# CH32L103C8T-R0.net
KiCad netlist of a schematic drawn in Altium Designer
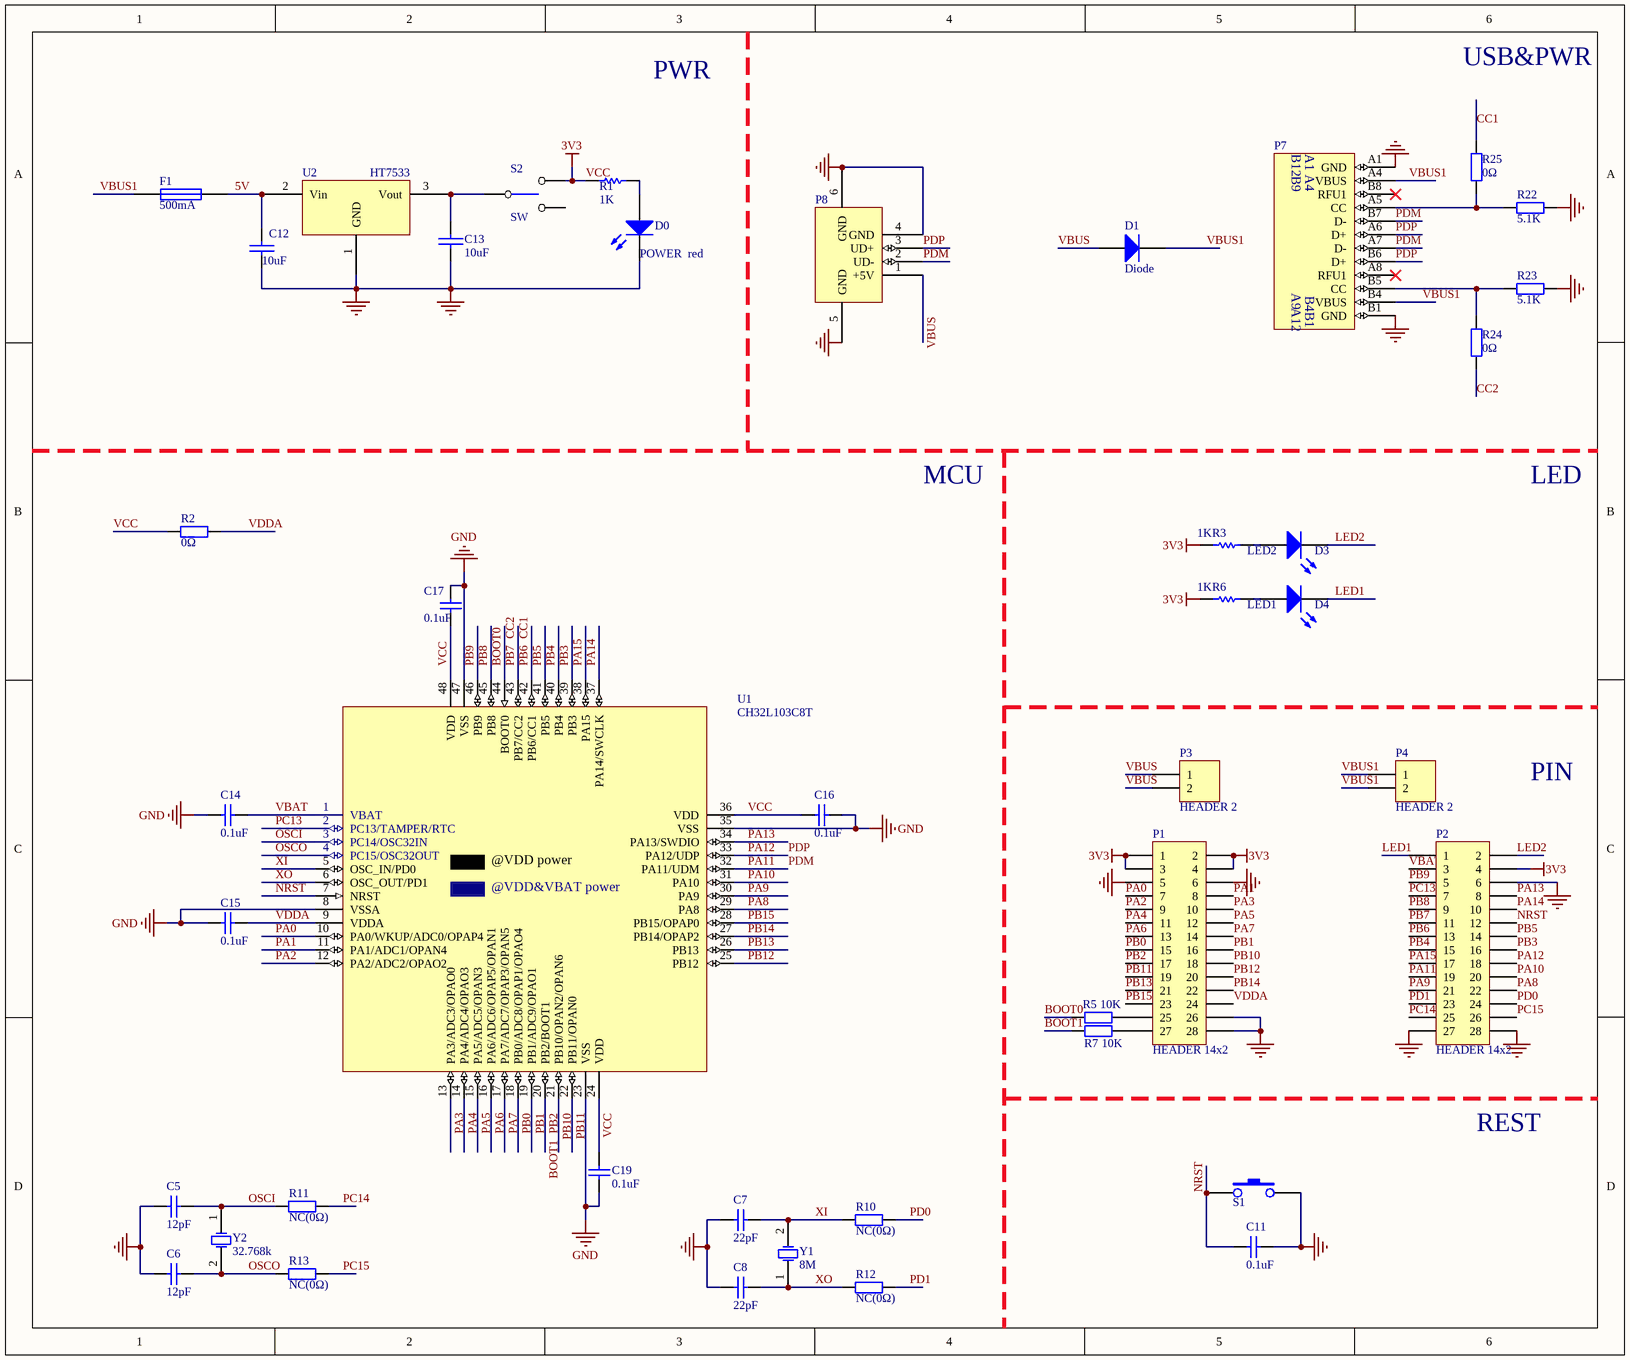
[diagram p0: CH32L103C8T-R0.SchDoc]

(export (version "E")
  (design (tool "Eeschema 10.0.6"))
  (components
    (comp (ref "C5")
      (value "12pF")
      (footprint "0402_C")
      (description "Capacitor")
      (fields (field (name "PUBLISHER") "Altium Limited"))
      (libsource (lib "*") (part "Cap"))
    )
    (comp (ref "C6")
      (value "12pF")
      (footprint "0402_C")
      (description "Capacitor")
      (fields (field (name "PUBLISHER") "Altium Limited"))
      (libsource (lib "*") (part "Cap"))
    )
    (comp (ref "C7")
      (value "22pF")
      (footprint "0402_C")
      (description "Capacitor")
      (fields (field (name "PUBLISHER") "Altium Limited"))
      (libsource (lib "*") (part "Cap"))
    )
    (comp (ref "C8")
      (value "22pF")
      (footprint "0402_C")
      (description "Capacitor")
      (fields (field (name "PUBLISHER") "Altium Limited"))
      (libsource (lib "*") (part "Cap"))
    )
    (comp (ref "C11")
      (value "0.1uF")
      (footprint "0402_C")
      (description "Capacitor")
      (fields (field (name "PUBLISHER") "Altium Limited"))
      (libsource (lib "*") (part "Cap"))
    )
    (comp (ref "C12")
      (value "10uF")
      (footprint "0603_C")
      (description "Capacitor")
      (libsource (lib "*") (part "CAP"))
    )
    (comp (ref "C13")
      (value "10uF")
      (footprint "0603_C")
      (description "Capacitor")
      (libsource (lib "*") (part "CAP"))
    )
    (comp (ref "C14")
      (value "0.1uF")
      (footprint "0402_C")
      (description "Capacitor")
      (fields (field (name "PUBLISHER") "Altium Limited"))
      (libsource (lib "*") (part "Cap"))
    )
    (comp (ref "C15")
      (value "0.1uF")
      (footprint "0402_C")
      (description "Capacitor")
      (fields (field (name "PUBLISHER") "Altium Limited"))
      (libsource (lib "*") (part "Cap"))
    )
    (comp (ref "C16")
      (value "0.1uF")
      (footprint "0402_C")
      (description "Capacitor")
      (fields (field (name "PUBLISHER") "Altium Limited"))
      (libsource (lib "*") (part "Cap"))
    )
    (comp (ref "C17")
      (value "0.1uF")
      (footprint "0402_C")
      (description "Capacitor")
      (fields (field (name "PUBLISHER") "Altium Limited"))
      (libsource (lib "*") (part "Cap"))
    )
    (comp (ref "C19")
      (value "0.1uF")
      (footprint "0402_C")
      (description "Capacitor")
      (fields (field (name "PUBLISHER") "Altium Limited"))
      (libsource (lib "*") (part "Cap"))
    )
    (comp (ref "D0")
      (value "POWER  red")
      (footprint "0603+")
      (description "Typical INFRARED GaAs LED")
      (fields (field (name "PUBLISHER") "Altium Limited"))
      (libsource (lib "*") (part "LED0"))
    )
    (comp (ref "D1")
      (value "Diode")
      (footprint "SOD-123")
      (description "Default Diode")
      (fields (field (name "PUBLISHER") "Altium Limited"))
      (libsource (lib "Miscellaneous Devices") (part "Diode"))
    )
    (comp (ref "D3")
      (value "LED2")
      (footprint "0603+")
      (description "Typical INFRARED GaAs LED")
      (fields (field (name "PUBLISHER") "Altium Limited"))
      (libsource (lib "*") (part "LED0"))
    )
    (comp (ref "D4")
      (value "LED1")
      (footprint "0603+")
      (description "Typical INFRARED GaAs LED")
      (fields (field (name "PUBLISHER") "Altium Limited"))
      (libsource (lib "*") (part "LED0"))
    )
    (comp (ref "F1")
      (value "500mA")
      (footprint "0603")
      (description "Fuse")
      (libsource (lib "*") (part "FUSE1"))
    )
    (comp (ref "P1")
      (value "HEADER 14x2")
      (footprint "MYPCB:IDC28-2.54MM")
      (description "Header, 14-Pin, Dual row")
      (libsource (lib "wch_sch_others") (part "HEADER 14x2"))
    )
    (comp (ref "P2")
      (value "HEADER 14x2")
      (footprint "MYPCB:IDC28-2.54MM")
      (description "Header, 14-Pin, Dual row")
      (libsource (lib "wch_sch_others") (part "HEADER 14x2"))
    )
    (comp (ref "P3")
      (value "HEADER 2")
      (footprint "SIP2-2.54mm")
      (description "Header, 2-Pin")
      (libsource (lib "wch_sch_others") (part "HEADER 2"))
    )
    (comp (ref "P4")
      (value "HEADER 2")
      (footprint "SIP2-2.54mm")
      (description "Header, 2-Pin")
      (libsource (lib "wch_sch_others") (part "HEADER 2"))
    )
    (comp (ref "P7")
      (value "TYPE-C")
      (footprint "TYPE-C-Receptacle-2.0")
      (libsource (lib "*") (part "TYPE-C1"))
    )
    (comp (ref "P8")
      (value "USB_A")
      (footprint "USBAF")
      (description "USB Port")
      (libsource (lib "*") (part "USB"))
    )
    (comp (ref "R1")
      (value "1K")
      (footprint "0402")
      (description "Semiconductor Resistor")
      (libsource (lib "*") (part "Res Semi"))
    )
    (comp (ref "R2")
      (value "0Ω")
      (footprint "0402")
      (description "Resistor")
      (libsource (lib "Miscellaneous Devices") (part "Res2"))
    )
    (comp (ref "R3")
      (value "1K")
      (footprint "0402")
      (description "Semiconductor Resistor")
      (libsource (lib "*") (part "Res Semi"))
    )
    (comp (ref "R5")
      (value "10K")
      (footprint "0402")
      (description "Resistor")
      (fields (field (name "PUBLISHER") "Altium Limited"))
      (libsource (lib "*") (part "Res2"))
    )
    (comp (ref "R6")
      (value "1K")
      (footprint "0402")
      (description "Semiconductor Resistor")
      (libsource (lib "*") (part "Res Semi"))
    )
    (comp (ref "R7")
      (value "10K")
      (footprint "0402")
      (description "Resistor")
      (fields (field (name "PUBLISHER") "Altium Limited"))
      (libsource (lib "*") (part "Res2"))
    )
    (comp (ref "R10")
      (value "NC(0Ω)")
      (footprint "0402")
      (description "Resistor")
      (libsource (lib "") (part "Res2_2"))
    )
    (comp (ref "R11")
      (value "NC(0Ω)")
      (footprint "0402")
      (description "Resistor")
      (libsource (lib "") (part "Res2_2"))
    )
    (comp (ref "R12")
      (value "NC(0Ω)")
      (footprint "0402")
      (description "Resistor")
      (libsource (lib "") (part "Res2_2"))
    )
    (comp (ref "R13")
      (value "NC(0Ω)")
      (footprint "0402")
      (description "Resistor")
      (libsource (lib "") (part "Res2_2"))
    )
    (comp (ref "R22")
      (value "5.1K")
      (footprint "0402")
      (description "Resistor")
      (libsource (lib "Miscellaneous Devices") (part "Res2"))
    )
    (comp (ref "R23")
      (value "5.1K")
      (footprint "0402")
      (description "Resistor")
      (libsource (lib "Miscellaneous Devices") (part "Res2"))
    )
    (comp (ref "R24")
      (value "0Ω")
      (footprint "0402")
      (description "Resistor")
      (libsource (lib "") (part "Res2_1"))
    )
    (comp (ref "R25")
      (value "0Ω")
      (footprint "0402")
      (description "Resistor")
      (libsource (lib "") (part "Res2_1"))
    )
    (comp (ref "S1") (value "KEY") (footprint "SMD_6.1x3.65x2.5mm-KEY") (libsource (lib "*") (part "KEY")))
    (comp (ref "S2") (value "SW") (footprint "SW1") (libsource (lib "*") (part "SW")))
    (comp (ref "U1")
      (value "CH32L103C8T")
      (footprint "LQFP48")
      (description "RISC-V LMD-MCU, 96MHz, USB, Type-C/PD, CAN, OPA, lower power")
      (libsource (lib "CHXXX") (part "CH32L103C8T"))
    )
    (comp (ref "U2")
      (value "HT7533")
      (footprint "SOT-89")
      (libsource (lib "wch_sch_others") (part "1117-3.3V"))
    )
    (comp (ref "Y1")
      (value "8M")
      (footprint "XT3225")
      (description "Crystal Oscillator")
      (fields (field (name "PUBLISHER") "Altium Limited"))
      (libsource (lib "*") (part "XTAL"))
    )
    (comp (ref "Y2")
      (value "32.768k")
      (footprint "FC-135")
      (description "Crystal Oscillator")
      (fields (field (name "PUBLISHER") "Altium Limited"))
      (libsource (lib "*") (part "XTAL"))
    )
  )
  (nets
    (net (code "1") (name "/5V") (class "Default")
      (node (ref "C12") (pin "1") (pinfunction "1_1") (pintype "passive"))
      (node (ref "F1") (pin "2") (pinfunction "2_2") (pintype "passive"))
      (node (ref "U2") (pin "2") (pinfunction "Vin_2") (pintype "passive"))
    )
    (net (code "3") (name "/BOOT0") (class "Default")
      (node (ref "R5") (pin "1") (pinfunction "1_1") (pintype "passive"))
      (node (ref "U1") (pin "44") (pinfunction "BOOT0_44") (pintype "input"))
    )
    (net (code "4") (name "/BOOT1") (class "Default")
      (node (ref "P1") (pin "17") (pinfunction "17_17") (pintype "passive"))
      (node (ref "R7") (pin "1") (pinfunction "1_1") (pintype "passive"))
      (node (ref "U1") (pin "20") (pinfunction "PB2/BOOT1_20") (pintype "bidirectional"))
    )
    (net (code "5") (name "/CC1") (class "Default")
      (node (ref "P2") (pin "13") (pinfunction "13_13") (pintype "passive"))
      (node (ref "R25") (pin "2") (pinfunction "2_2") (pintype "passive"))
      (node (ref "U1") (pin "42") (pinfunction "PB6/CC1_42") (pintype "bidirectional"))
    )
    (net (code "6") (name "/CC2") (class "Default")
      (node (ref "P2") (pin "11") (pinfunction "11_11") (pintype "passive"))
      (node (ref "R24") (pin "1") (pinfunction "1_1") (pintype "passive"))
      (node (ref "U1") (pin "43") (pinfunction "PB7/CC2_43") (pintype "bidirectional"))
    )
    (net (code "7") (name "/LED1") (class "Default")
      (node (ref "D4") (pin "2") (pinfunction "K_2") (pintype "passive"))
      (node (ref "P2") (pin "1") (pinfunction "1_1") (pintype "passive"))
    )
    (net (code "8") (name "/LED2") (class "Default")
      (node (ref "D3") (pin "2") (pinfunction "K_2") (pintype "passive"))
      (node (ref "P2") (pin "2") (pinfunction "2_2") (pintype "passive"))
    )
    (net (code "9") (name "/NRST") (class "Default")
      (node (ref "C11") (pin "2") (pinfunction "2_2") (pintype "passive"))
      (node (ref "P2") (pin "12") (pinfunction "12_12") (pintype "passive"))
      (node (ref "S1") (pin "1") (pinfunction "1_1") (pintype "passive"))
      (node (ref "U1") (pin "7") (pinfunction "NRST_7") (pintype "input"))
    )
    (net (code "10") (name "/OSCI") (class "Default")
      (node (ref "C5") (pin "1") (pinfunction "1_1") (pintype "passive"))
      (node (ref "R11") (pin "2") (pinfunction "2_2") (pintype "passive"))
      (node (ref "U1") (pin "3") (pinfunction "PC14/OSC32IN_3") (pintype "bidirectional"))
      (node (ref "Y2") (pin "1") (pinfunction "OSC1_1") (pintype "passive"))
    )
    (net (code "11") (name "/OSCO") (class "Default")
      (node (ref "C6") (pin "1") (pinfunction "1_1") (pintype "passive"))
      (node (ref "R13") (pin "2") (pinfunction "2_2") (pintype "passive"))
      (node (ref "U1") (pin "4") (pinfunction "PC15/OSC32OUT_4") (pintype "bidirectional"))
      (node (ref "Y2") (pin "2") (pinfunction "OSC2_2") (pintype "passive"))
    )
    (net (code "12") (name "/PA0") (class "Default")
      (node (ref "P1") (pin "7") (pinfunction "7_7") (pintype "passive"))
      (node (ref "U1") (pin "10") (pinfunction "PA0/WKUP/ADC0/OPAP4_10") (pintype "bidirectional"))
    )
    (net (code "13") (name "/PA1") (class "Default")
      (node (ref "P1") (pin "8") (pinfunction "8_8") (pintype "passive"))
      (node (ref "U1") (pin "11") (pinfunction "PA1/ADC1/OPAN4_11") (pintype "bidirectional"))
    )
    (net (code "14") (name "/PA2") (class "Default")
      (node (ref "P1") (pin "9") (pinfunction "9_9") (pintype "passive"))
      (node (ref "U1") (pin "12") (pinfunction "PA2/ADC2/OPAO2_12") (pintype "bidirectional"))
    )
    (net (code "15") (name "/PA3") (class "Default")
      (node (ref "P1") (pin "10") (pinfunction "10_10") (pintype "passive"))
      (node (ref "U1") (pin "13") (pinfunction "PA3/ADC3/OPAO0_13") (pintype "bidirectional"))
    )
    (net (code "16") (name "/PA4") (class "Default")
      (node (ref "P1") (pin "11") (pinfunction "11_11") (pintype "passive"))
      (node (ref "U1") (pin "14") (pinfunction "PA4/ADC4/OPAO3_14") (pintype "bidirectional"))
    )
    (net (code "17") (name "/PA5") (class "Default")
      (node (ref "P1") (pin "12") (pinfunction "12_12") (pintype "passive"))
      (node (ref "U1") (pin "15") (pinfunction "PA5/ADC5/OPAN3_15") (pintype "bidirectional"))
    )
    (net (code "18") (name "/PA6") (class "Default")
      (node (ref "P1") (pin "13") (pinfunction "13_13") (pintype "passive"))
      (node (ref "U1") (pin "16") (pinfunction "PA6/ADC6/OPAP5/OPAN1_16") (pintype "bidirectional"))
    )
    (net (code "19") (name "/PA7") (class "Default")
      (node (ref "P1") (pin "14") (pinfunction "14_14") (pintype "passive"))
      (node (ref "U1") (pin "17") (pinfunction "PA7/ADC7/OPAP3/OPAN5_17") (pintype "bidirectional"))
    )
    (net (code "20") (name "/PA8") (class "Default")
      (node (ref "P2") (pin "22") (pinfunction "22_22") (pintype "passive"))
      (node (ref "U1") (pin "29") (pinfunction "PA8_29") (pintype "bidirectional"))
    )
    (net (code "21") (name "/PA9") (class "Default")
      (node (ref "P2") (pin "21") (pinfunction "21_21") (pintype "passive"))
      (node (ref "U1") (pin "30") (pinfunction "PA9_30") (pintype "bidirectional"))
    )
    (net (code "22") (name "/PA10") (class "Default")
      (node (ref "P2") (pin "20") (pinfunction "20_20") (pintype "passive"))
      (node (ref "U1") (pin "31") (pinfunction "PA10_31") (pintype "bidirectional"))
    )
    (net (code "23") (name "/PA11") (class "Default")
      (node (ref "P2") (pin "19") (pinfunction "19_19") (pintype "passive"))
      (node (ref "P7") (pin "A7") (pinfunction "D-_A7") (pintype "bidirectional"))
      (node (ref "P7") (pin "B7") (pinfunction "D-_B7") (pintype "bidirectional"))
      (node (ref "P8") (pin "2") (pinfunction "UD-_2") (pintype "bidirectional"))
      (node (ref "U1") (pin "32") (pinfunction "PA11/UDM_32") (pintype "bidirectional"))
    )
    (net (code "24") (name "/PA12") (class "Default")
      (node (ref "P2") (pin "18") (pinfunction "18_18") (pintype "passive"))
      (node (ref "P7") (pin "A6") (pinfunction "D+_A6") (pintype "bidirectional"))
      (node (ref "P7") (pin "B6") (pinfunction "D+_B6") (pintype "bidirectional"))
      (node (ref "P8") (pin "3") (pinfunction "UD+_3") (pintype "bidirectional"))
      (node (ref "U1") (pin "33") (pinfunction "PA12/UDP_33") (pintype "bidirectional"))
    )
    (net (code "25") (name "/PA13") (class "Default")
      (node (ref "P2") (pin "8") (pinfunction "8_8") (pintype "passive"))
      (node (ref "U1") (pin "34") (pinfunction "PA13/SWDIO_34") (pintype "bidirectional"))
    )
    (net (code "26") (name "/PA14") (class "Default")
      (node (ref "P2") (pin "10") (pinfunction "10_10") (pintype "passive"))
      (node (ref "U1") (pin "37") (pinfunction "PA14/SWCLK_37") (pintype "bidirectional"))
    )
    (net (code "27") (name "/PA15") (class "Default")
      (node (ref "P2") (pin "17") (pinfunction "17_17") (pintype "passive"))
      (node (ref "U1") (pin "38") (pinfunction "PA15_38") (pintype "bidirectional"))
    )
    (net (code "28") (name "/PB0") (class "Default")
      (node (ref "P1") (pin "15") (pinfunction "15_15") (pintype "passive"))
      (node (ref "U1") (pin "18") (pinfunction "PB0/ADC8/OPAP1/OPAO4_18") (pintype "bidirectional"))
    )
    (net (code "29") (name "/PB1") (class "Default")
      (node (ref "P1") (pin "16") (pinfunction "16_16") (pintype "passive"))
      (node (ref "U1") (pin "19") (pinfunction "PB1/ADC9/OPAO1_19") (pintype "bidirectional"))
    )
    (net (code "30") (name "/PB3") (class "Default")
      (node (ref "P2") (pin "16") (pinfunction "16_16") (pintype "passive"))
      (node (ref "U1") (pin "39") (pinfunction "PB3_39") (pintype "bidirectional"))
    )
    (net (code "31") (name "/PB4") (class "Default")
      (node (ref "P2") (pin "15") (pinfunction "15_15") (pintype "passive"))
      (node (ref "U1") (pin "40") (pinfunction "PB4_40") (pintype "bidirectional"))
    )
    (net (code "32") (name "/PB5") (class "Default")
      (node (ref "P2") (pin "14") (pinfunction "14_14") (pintype "passive"))
      (node (ref "U1") (pin "41") (pinfunction "PB5_41") (pintype "bidirectional"))
    )
    (net (code "33") (name "/PB8") (class "Default")
      (node (ref "P2") (pin "9") (pinfunction "9_9") (pintype "passive"))
      (node (ref "U1") (pin "45") (pinfunction "PB8_45") (pintype "bidirectional"))
    )
    (net (code "34") (name "/PB9") (class "Default")
      (node (ref "P2") (pin "5") (pinfunction "5_5") (pintype "passive"))
      (node (ref "U1") (pin "46") (pinfunction "PB9_46") (pintype "bidirectional"))
    )
    (net (code "35") (name "/PB10") (class "Default")
      (node (ref "P1") (pin "18") (pinfunction "18_18") (pintype "passive"))
      (node (ref "U1") (pin "21") (pinfunction "PB10/OPAN2/OPAN6_21") (pintype "bidirectional"))
    )
    (net (code "36") (name "/PB11") (class "Default")
      (node (ref "P1") (pin "19") (pinfunction "19_19") (pintype "passive"))
      (node (ref "U1") (pin "22") (pinfunction "PB11/OPAN0_22") (pintype "bidirectional"))
    )
    (net (code "37") (name "/PB12") (class "Default")
      (node (ref "P1") (pin "20") (pinfunction "20_20") (pintype "passive"))
      (node (ref "U1") (pin "25") (pinfunction "PB12_25") (pintype "bidirectional"))
    )
    (net (code "38") (name "/PB13") (class "Default")
      (node (ref "P1") (pin "21") (pinfunction "21_21") (pintype "passive"))
      (node (ref "U1") (pin "26") (pinfunction "PB13_26") (pintype "bidirectional"))
    )
    (net (code "39") (name "/PB14") (class "Default")
      (node (ref "P1") (pin "22") (pinfunction "22_22") (pintype "passive"))
      (node (ref "U1") (pin "27") (pinfunction "PB14/OPAP2_27") (pintype "bidirectional"))
    )
    (net (code "40") (name "/PB15") (class "Default")
      (node (ref "P1") (pin "23") (pinfunction "23_23") (pintype "passive"))
      (node (ref "U1") (pin "28") (pinfunction "PB15/OPAP0_28") (pintype "bidirectional"))
    )
    (net (code "41") (name "/PC13") (class "Default")
      (node (ref "P2") (pin "7") (pinfunction "7_7") (pintype "passive"))
      (node (ref "U1") (pin "2") (pinfunction "PC13/TAMPER/RTC_2") (pintype "bidirectional"))
    )
    (net (code "42") (name "/PC14") (class "Default")
      (node (ref "P2") (pin "25") (pinfunction "25_25") (pintype "passive"))
      (node (ref "R11") (pin "1") (pinfunction "1_1") (pintype "passive"))
    )
    (net (code "43") (name "/PC15") (class "Default")
      (node (ref "P2") (pin "26") (pinfunction "26_26") (pintype "passive"))
      (node (ref "R13") (pin "1") (pinfunction "1_1") (pintype "passive"))
    )
    (net (code "44") (name "/PD0") (class "Default")
      (node (ref "P2") (pin "24") (pinfunction "24_24") (pintype "passive"))
      (node (ref "R10") (pin "1") (pinfunction "1_1") (pintype "passive"))
    )
    (net (code "45") (name "/PD1") (class "Default")
      (node (ref "P2") (pin "23") (pinfunction "23_23") (pintype "passive"))
      (node (ref "R12") (pin "1") (pinfunction "1_1") (pintype "passive"))
    )
    (net (code "46") (name "/VBAT") (class "Default")
      (node (ref "C14") (pin "1") (pinfunction "1_1") (pintype "passive"))
      (node (ref "P2") (pin "3") (pinfunction "3_3") (pintype "passive"))
      (node (ref "U1") (pin "1") (pinfunction "VBAT_1") (pintype "power_in"))
    )
    (net (code "47") (name "/VBUS") (class "Default")
      (node (ref "D1") (pin "1") (pinfunction "A_1") (pintype "passive"))
      (node (ref "P3") (pin "1") (pinfunction "1_1") (pintype "passive"))
      (node (ref "P3") (pin "2") (pinfunction "2_2") (pintype "passive"))
      (node (ref "P8") (pin "1") (pinfunction "+5V_1") (pintype "power_in"))
    )
    (net (code "48") (name "/VBUS1") (class "Default")
      (node (ref "D1") (pin "2") (pinfunction "K_2") (pintype "passive"))
      (node (ref "F1") (pin "1") (pinfunction "1_1") (pintype "passive"))
      (node (ref "P4") (pin "1") (pinfunction "1_1") (pintype "passive"))
      (node (ref "P4") (pin "2") (pinfunction "2_2") (pintype "passive"))
      (node (ref "P7") (pin "A4") (pinfunction "VBUS_A4") (pintype "bidirectional"))
      (node (ref "P7") (pin "B4") (pinfunction "VBUS_B4") (pintype "bidirectional"))
    )
    (net (code "49") (name "/VDDA") (class "Default")
      (node (ref "C15") (pin "1") (pinfunction "1_1") (pintype "passive"))
      (node (ref "P1") (pin "24") (pinfunction "24_24") (pintype "passive"))
      (node (ref "R2") (pin "2") (pinfunction "2_2") (pintype "passive"))
      (node (ref "U1") (pin "9") (pinfunction "VDDA_9") (pintype "power_in"))
    )
    (net (code "50") (name "/XI") (class "Default")
      (node (ref "C7") (pin "2") (pinfunction "2_2") (pintype "passive"))
      (node (ref "R10") (pin "2") (pinfunction "2_2") (pintype "passive"))
      (node (ref "U1") (pin "5") (pinfunction "OSC_IN/PD0_5") (pintype "bidirectional"))
      (node (ref "Y1") (pin "2") (pinfunction "OSC2_2") (pintype "passive"))
    )
    (net (code "51") (name "/XO") (class "Default")
      (node (ref "C8") (pin "2") (pinfunction "2_2") (pintype "passive"))
      (node (ref "R12") (pin "2") (pinfunction "2_2") (pintype "passive"))
      (node (ref "U1") (pin "6") (pinfunction "OSC_OUT/PD1_6") (pintype "bidirectional"))
      (node (ref "Y1") (pin "1") (pinfunction "OSC1_1") (pintype "passive"))
    )
    (net (code "52") (name "3V3") (class "Default")
      (node (ref "C16") (pin "1") (pinfunction "1_1") (pintype "passive"))
      (node (ref "C17") (pin "2") (pinfunction "2_2") (pintype "passive"))
      (node (ref "C19") (pin "2") (pinfunction "2_2") (pintype "passive"))
      (node (ref "P1") (pin "1") (pinfunction "1_1") (pintype "passive"))
      (node (ref "P1") (pin "2") (pinfunction "2_2") (pintype "passive"))
      (node (ref "P1") (pin "3") (pinfunction "3_3") (pintype "passive"))
      (node (ref "P1") (pin "4") (pinfunction "4_4") (pintype "passive"))
      (node (ref "P2") (pin "4") (pinfunction "4_4") (pintype "passive"))
      (node (ref "R1") (pin "2") (pinfunction "2_2") (pintype "passive"))
      (node (ref "R2") (pin "1") (pinfunction "1_1") (pintype "passive"))
      (node (ref "R3") (pin "1") (pinfunction "1_1") (pintype "passive"))
      (node (ref "R6") (pin "1") (pinfunction "1_1") (pintype "passive"))
      (node (ref "S2") (pin "3") (pinfunction "3_3") (pintype "passive"))
      (node (ref "U1") (pin "24") (pinfunction "VDD_24") (pintype "power_in"))
      (node (ref "U1") (pin "36") (pinfunction "VDD_36") (pintype "power_in"))
      (node (ref "U1") (pin "48") (pinfunction "VDD_48") (pintype "power_in"))
    )
    (net (code "53") (name "GND") (class "Default")
      (node (ref "C11") (pin "1") (pinfunction "1_1") (pintype "passive"))
      (node (ref "C12") (pin "2") (pinfunction "2_2") (pintype "passive"))
      (node (ref "C13") (pin "2") (pinfunction "2_2") (pintype "passive"))
      (node (ref "C14") (pin "2") (pinfunction "2_2") (pintype "passive"))
      (node (ref "C15") (pin "2") (pinfunction "2_2") (pintype "passive"))
      (node (ref "C16") (pin "2") (pinfunction "2_2") (pintype "passive"))
      (node (ref "C17") (pin "1") (pinfunction "1_1") (pintype "passive"))
      (node (ref "C19") (pin "1") (pinfunction "1_1") (pintype "passive"))
      (node (ref "C5") (pin "2") (pinfunction "2_2") (pintype "passive"))
      (node (ref "C6") (pin "2") (pinfunction "2_2") (pintype "passive"))
      (node (ref "C7") (pin "1") (pinfunction "1_1") (pintype "passive"))
      (node (ref "C8") (pin "1") (pinfunction "1_1") (pintype "passive"))
      (node (ref "D0") (pin "2") (pinfunction "K_2") (pintype "passive"))
      (node (ref "P1") (pin "26") (pinfunction "26_26") (pintype "passive"))
      (node (ref "P1") (pin "28") (pinfunction "28_28") (pintype "passive"))
      (node (ref "P1") (pin "5") (pinfunction "5_5") (pintype "passive"))
      (node (ref "P1") (pin "6") (pinfunction "6_6") (pintype "passive"))
      (node (ref "P2") (pin "27") (pinfunction "27_27") (pintype "passive"))
      (node (ref "P2") (pin "28") (pinfunction "28_28") (pintype "passive"))
      (node (ref "P2") (pin "6") (pinfunction "6_6") (pintype "passive"))
      (node (ref "P7") (pin "A1") (pinfunction "GND_A1") (pintype "bidirectional"))
      (node (ref "P7") (pin "B1") (pinfunction "GND_B1") (pintype "bidirectional"))
      (node (ref "P8") (pin "4") (pinfunction "GND_4") (pintype "power_in"))
      (node (ref "P8") (pin "5") (pinfunction "GND_5") (pintype "power_in"))
      (node (ref "P8") (pin "6") (pinfunction "GND_6") (pintype "power_in"))
      (node (ref "R22") (pin "2") (pinfunction "2_2") (pintype "passive"))
      (node (ref "R23") (pin "2") (pinfunction "2_2") (pintype "passive"))
      (node (ref "S1") (pin "2") (pinfunction "2_2") (pintype "passive"))
      (node (ref "U1") (pin "23") (pinfunction "VSS_23") (pintype "power_in"))
      (node (ref "U1") (pin "35") (pinfunction "VSS_35") (pintype "power_in"))
      (node (ref "U1") (pin "47") (pinfunction "VSS_47") (pintype "power_in"))
      (node (ref "U1") (pin "8") (pinfunction "VSSA_8") (pintype "power_in"))
      (node (ref "U2") (pin "1") (pinfunction "GND_1") (pintype "passive"))
    )
    (net (code "54") (name "Net-(D0-A)") (class "Default")
      (node (ref "D0") (pin "1") (pinfunction "A_1") (pintype "passive"))
      (node (ref "R1") (pin "1") (pinfunction "1_1") (pintype "passive"))
    )
    (net (code "55") (name "Net-(D3-A)") (class "Default")
      (node (ref "D3") (pin "1") (pinfunction "A_1") (pintype "passive"))
      (node (ref "R3") (pin "2") (pinfunction "2_2") (pintype "passive"))
    )
    (net (code "56") (name "Net-(D4-A)") (class "Default")
      (node (ref "D4") (pin "1") (pinfunction "A_1") (pintype "passive"))
      (node (ref "R6") (pin "2") (pinfunction "2_2") (pintype "passive"))
    )
    (net (code "57") (name "Net-(P1-Pad25)") (class "Default")
      (node (ref "P1") (pin "25") (pinfunction "25_25") (pintype "passive"))
      (node (ref "R5") (pin "2") (pinfunction "2_2") (pintype "passive"))
    )
    (net (code "58") (name "Net-(P1-Pad27)") (class "Default")
      (node (ref "P1") (pin "27") (pinfunction "27_27") (pintype "passive"))
      (node (ref "R7") (pin "2") (pinfunction "2_2") (pintype "passive"))
    )
    (net (code "59") (name "Net-(P7-CC-PadA5)") (class "Default")
      (node (ref "P7") (pin "A5") (pinfunction "CC_A5") (pintype "bidirectional"))
      (node (ref "R22") (pin "1") (pinfunction "1_1") (pintype "passive"))
      (node (ref "R25") (pin "1") (pinfunction "1_1") (pintype "passive"))
    )
    (net (code "60") (name "Net-(P7-CC-PadB5)") (class "Default")
      (node (ref "P7") (pin "B5") (pinfunction "CC_B5") (pintype "bidirectional"))
      (node (ref "R23") (pin "1") (pinfunction "1_1") (pintype "passive"))
      (node (ref "R24") (pin "2") (pinfunction "2_2") (pintype "passive"))
    )
    (net (code "61") (name "Net-(U2-Vout)") (class "Default")
      (node (ref "C13") (pin "1") (pinfunction "1_1") (pintype "passive"))
      (node (ref "S2") (pin "1") (pinfunction "1_1") (pintype "passive"))
      (node (ref "U2") (pin "3") (pinfunction "Vout_3") (pintype "passive"))
    )
    (net (code "62") (name "unconnected-(P7-RFU1-PadA8)") (class "Default")
      (node (ref "P7") (pin "A8") (pinfunction "RFU1_A8") (pintype "bidirectional+no_connect"))
    )
    (net (code "63") (name "unconnected-(P7-RFU1-PadB8)") (class "Default")
      (node (ref "P7") (pin "B8") (pinfunction "RFU1_B8") (pintype "bidirectional+no_connect"))
    )
    (net (code "64") (name "unconnected-(S2-Pad2)") (class "Default")
      (node (ref "S2") (pin "2") (pinfunction "2_2") (pintype "passive"))
    )
  )
)
